# RN52_BO.net
KiCad netlist of a schematic drawn in EAGLE
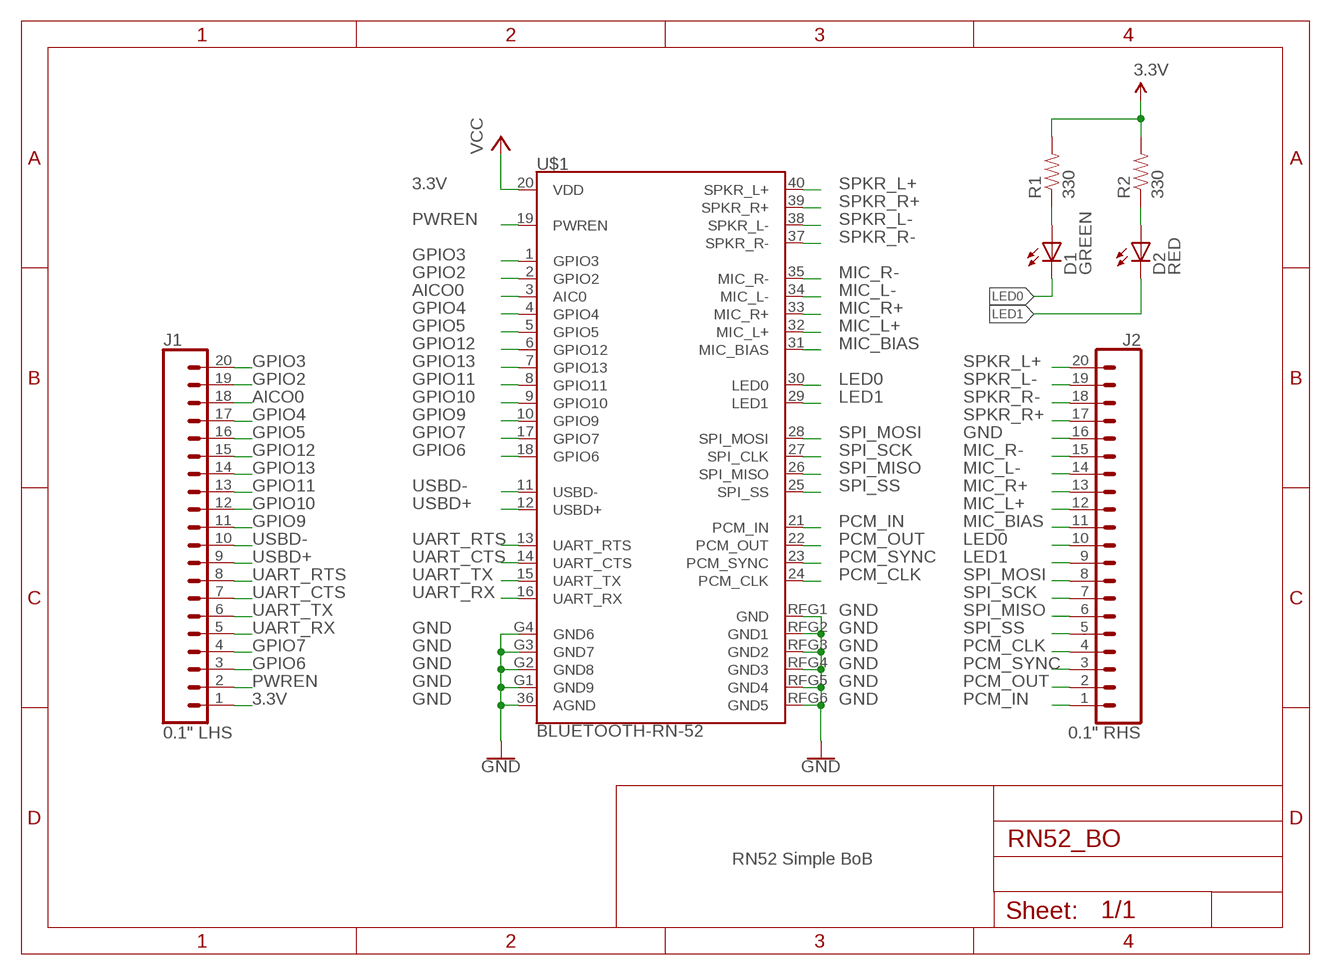
[diagram p0: schematic, sheet 1]

(export (version "E")
  (design (tool "Eeschema 10.0.6"))
  (components
    (comp (ref "D1")
      (value "GREEN")
      (footprint "eagle-import:LED-0603")
      (libsource (lib "eagle-import") (part "LED-GREEN0603"))
    )
    (comp (ref "D2")
      (value "RED")
      (footprint "eagle-import:LED-0603")
      (libsource (lib "eagle-import") (part "LED-RED0603"))
    )
    (comp (ref "J1")
      (value "0.1\" LHS")
      (footprint "eagle-import:1X20")
      (fields (field (name "TITLE") "0.1\" LHS"))
      (libsource (lib "eagle-import") (part "CONN_20"))
    )
    (comp (ref "J2")
      (value "0.1\" RHS")
      (footprint "eagle-import:1X20")
      (fields (field (name "TITLE") "0.1\" RHS"))
      (libsource (lib "eagle-import") (part "CONN_20"))
    )
    (comp (ref "R1")
      (value "330")
      (footprint "eagle-import:0603-RES")
      (libsource (lib "eagle-import") (part "RESISTOR0603-RES"))
    )
    (comp (ref "R2")
      (value "330")
      (footprint "eagle-import:0603-RES")
      (libsource (lib "eagle-import") (part "RESISTOR0603-RES"))
    )
    (comp (ref "U$1")
      (value "BLUETOOTH-RN-52")
      (footprint "eagle-import:RN-52")
      (libsource (lib "eagle-import") (part "BLUETOOTH-RN-52"))
    )
  )
  (nets
    (net (code "1") (name "/AICO0") (class "Default")
      (node (ref "J1") (pin "18") (pinfunction "18_18") (pintype "passive"))
      (node (ref "U$1") (pin "3") (pinfunction "AIC0_3") (pintype "bidirectional"))
    )
    (net (code "2") (name "/GPIO2") (class "Default")
      (node (ref "J1") (pin "19") (pinfunction "19_19") (pintype "passive"))
      (node (ref "U$1") (pin "2") (pinfunction "GPIO2_2") (pintype "bidirectional"))
    )
    (net (code "3") (name "/GPIO3") (class "Default")
      (node (ref "J1") (pin "20") (pinfunction "20_20") (pintype "passive"))
      (node (ref "U$1") (pin "1") (pinfunction "GPIO3_1") (pintype "bidirectional"))
    )
    (net (code "4") (name "/GPIO4") (class "Default")
      (node (ref "J1") (pin "17") (pinfunction "17_17") (pintype "passive"))
      (node (ref "U$1") (pin "4") (pinfunction "GPIO4_4") (pintype "bidirectional"))
    )
    (net (code "5") (name "/GPIO5") (class "Default")
      (node (ref "J1") (pin "16") (pinfunction "16_16") (pintype "passive"))
      (node (ref "U$1") (pin "5") (pinfunction "GPIO5_5") (pintype "bidirectional"))
    )
    (net (code "6") (name "/GPIO6") (class "Default")
      (node (ref "J1") (pin "3") (pinfunction "3_3") (pintype "passive"))
      (node (ref "U$1") (pin "18") (pinfunction "GPIO6_18") (pintype "bidirectional"))
    )
    (net (code "7") (name "/GPIO7") (class "Default")
      (node (ref "J1") (pin "4") (pinfunction "4_4") (pintype "passive"))
      (node (ref "U$1") (pin "17") (pinfunction "GPIO7_17") (pintype "bidirectional"))
    )
    (net (code "8") (name "/GPIO9") (class "Default")
      (node (ref "J1") (pin "11") (pinfunction "11_11") (pintype "passive"))
      (node (ref "U$1") (pin "10") (pinfunction "GPIO9_10") (pintype "bidirectional"))
    )
    (net (code "9") (name "/GPIO10") (class "Default")
      (node (ref "J1") (pin "12") (pinfunction "12_12") (pintype "passive"))
      (node (ref "U$1") (pin "9") (pinfunction "GPIO10_9") (pintype "bidirectional"))
    )
    (net (code "10") (name "/GPIO11") (class "Default")
      (node (ref "J1") (pin "13") (pinfunction "13_13") (pintype "passive"))
      (node (ref "U$1") (pin "8") (pinfunction "GPIO11_8") (pintype "bidirectional"))
    )
    (net (code "11") (name "/GPIO12") (class "Default")
      (node (ref "J1") (pin "15") (pinfunction "15_15") (pintype "passive"))
      (node (ref "U$1") (pin "6") (pinfunction "GPIO12_6") (pintype "bidirectional"))
    )
    (net (code "12") (name "/GPIO13") (class "Default")
      (node (ref "J1") (pin "14") (pinfunction "14_14") (pintype "passive"))
      (node (ref "U$1") (pin "7") (pinfunction "GPIO13_7") (pintype "bidirectional"))
    )
    (net (code "13") (name "/MIC_BIAS") (class "Default")
      (node (ref "J2") (pin "11") (pinfunction "11_11") (pintype "passive"))
      (node (ref "U$1") (pin "31") (pinfunction "MIC_BIAS_31") (pintype "bidirectional"))
    )
    (net (code "14") (name "/MIC_L+") (class "Default")
      (node (ref "J2") (pin "12") (pinfunction "12_12") (pintype "passive"))
      (node (ref "U$1") (pin "32") (pinfunction "MIC_L+_32") (pintype "bidirectional"))
    )
    (net (code "15") (name "/MIC_L-") (class "Default")
      (node (ref "J2") (pin "14") (pinfunction "14_14") (pintype "passive"))
      (node (ref "U$1") (pin "34") (pinfunction "MIC_L-_34") (pintype "bidirectional"))
    )
    (net (code "16") (name "/MIC_R+") (class "Default")
      (node (ref "J2") (pin "13") (pinfunction "13_13") (pintype "passive"))
      (node (ref "U$1") (pin "33") (pinfunction "MIC_R+_33") (pintype "bidirectional"))
    )
    (net (code "17") (name "/MIC_R-") (class "Default")
      (node (ref "J2") (pin "15") (pinfunction "15_15") (pintype "passive"))
      (node (ref "U$1") (pin "35") (pinfunction "MIC_R-_35") (pintype "bidirectional"))
    )
    (net (code "18") (name "/PCM_CLK") (class "Default")
      (node (ref "J2") (pin "4") (pinfunction "4_4") (pintype "passive"))
      (node (ref "U$1") (pin "24") (pinfunction "PCM_CLK_24") (pintype "bidirectional"))
    )
    (net (code "19") (name "/PCM_IN") (class "Default")
      (node (ref "J2") (pin "1") (pinfunction "1_1") (pintype "passive"))
      (node (ref "U$1") (pin "21") (pinfunction "PCM_IN_21") (pintype "bidirectional"))
    )
    (net (code "20") (name "/PCM_OUT") (class "Default")
      (node (ref "J2") (pin "2") (pinfunction "2_2") (pintype "passive"))
      (node (ref "U$1") (pin "22") (pinfunction "PCM_OUT_22") (pintype "bidirectional"))
    )
    (net (code "21") (name "/PCM_SYNC") (class "Default")
      (node (ref "J2") (pin "3") (pinfunction "3_3") (pintype "passive"))
      (node (ref "U$1") (pin "23") (pinfunction "PCM_SYNC_23") (pintype "bidirectional"))
    )
    (net (code "22") (name "/PWREN") (class "Default")
      (node (ref "J1") (pin "2") (pinfunction "2_2") (pintype "passive"))
      (node (ref "U$1") (pin "19") (pinfunction "PWREN_19") (pintype "bidirectional"))
    )
    (net (code "23") (name "/SPI_MISO") (class "Default")
      (node (ref "J2") (pin "6") (pinfunction "6_6") (pintype "passive"))
      (node (ref "U$1") (pin "26") (pinfunction "SPI_MISO_26") (pintype "bidirectional"))
    )
    (net (code "24") (name "/SPI_MOSI") (class "Default")
      (node (ref "J2") (pin "8") (pinfunction "8_8") (pintype "passive"))
      (node (ref "U$1") (pin "28") (pinfunction "SPI_MOSI_28") (pintype "bidirectional"))
    )
    (net (code "25") (name "/SPI_SCK") (class "Default")
      (node (ref "J2") (pin "7") (pinfunction "7_7") (pintype "passive"))
      (node (ref "U$1") (pin "27") (pinfunction "SPI_CLK_27") (pintype "bidirectional"))
    )
    (net (code "26") (name "/SPI_SS") (class "Default")
      (node (ref "J2") (pin "5") (pinfunction "5_5") (pintype "passive"))
      (node (ref "U$1") (pin "25") (pinfunction "SPI_SS_25") (pintype "bidirectional"))
    )
    (net (code "27") (name "/SPKR_L+") (class "Default")
      (node (ref "J2") (pin "20") (pinfunction "20_20") (pintype "passive"))
      (node (ref "U$1") (pin "40") (pinfunction "SPKR_L+_40") (pintype "bidirectional"))
    )
    (net (code "28") (name "/SPKR_L-") (class "Default")
      (node (ref "J2") (pin "19") (pinfunction "19_19") (pintype "passive"))
      (node (ref "U$1") (pin "38") (pinfunction "SPKR_L-_38") (pintype "bidirectional"))
    )
    (net (code "29") (name "/SPKR_R+") (class "Default")
      (node (ref "J2") (pin "17") (pinfunction "17_17") (pintype "passive"))
      (node (ref "U$1") (pin "39") (pinfunction "SPKR_R+_39") (pintype "bidirectional"))
    )
    (net (code "30") (name "/SPKR_R-") (class "Default")
      (node (ref "J2") (pin "18") (pinfunction "18_18") (pintype "passive"))
      (node (ref "U$1") (pin "37") (pinfunction "SPKR_R-_37") (pintype "bidirectional"))
    )
    (net (code "31") (name "/UART_CTS") (class "Default")
      (node (ref "J1") (pin "7") (pinfunction "7_7") (pintype "passive"))
      (node (ref "U$1") (pin "14") (pinfunction "UART_CTS_14") (pintype "bidirectional"))
    )
    (net (code "32") (name "/UART_RTS") (class "Default")
      (node (ref "J1") (pin "8") (pinfunction "8_8") (pintype "passive"))
      (node (ref "U$1") (pin "13") (pinfunction "UART_RTS_13") (pintype "bidirectional"))
    )
    (net (code "33") (name "/UART_RX") (class "Default")
      (node (ref "J1") (pin "5") (pinfunction "5_5") (pintype "passive"))
      (node (ref "U$1") (pin "16") (pinfunction "UART_RX_16") (pintype "bidirectional"))
    )
    (net (code "34") (name "/UART_TX") (class "Default")
      (node (ref "J1") (pin "6") (pinfunction "6_6") (pintype "passive"))
      (node (ref "U$1") (pin "15") (pinfunction "UART_TX_15") (pintype "bidirectional"))
    )
    (net (code "35") (name "/USBD+") (class "Default")
      (node (ref "J1") (pin "9") (pinfunction "9_9") (pintype "passive"))
      (node (ref "U$1") (pin "12") (pinfunction "USBD+_12") (pintype "bidirectional"))
    )
    (net (code "36") (name "/USBD-") (class "Default")
      (node (ref "J1") (pin "10") (pinfunction "10_10") (pintype "passive"))
      (node (ref "U$1") (pin "11") (pinfunction "USBD-_11") (pintype "bidirectional"))
    )
    (net (code "37") (name "3.3V") (class "Default")
      (node (ref "J1") (pin "1") (pinfunction "1_1") (pintype "passive"))
      (node (ref "R1") (pin "2") (pinfunction "2_2") (pintype "passive"))
      (node (ref "R2") (pin "2") (pinfunction "2_2") (pintype "passive"))
      (node (ref "U$1") (pin "20") (pinfunction "VDD_20") (pintype "bidirectional"))
    )
    (net (code "38") (name "GND") (class "Default")
      (node (ref "J2") (pin "16") (pinfunction "16_16") (pintype "passive"))
      (node (ref "U$1") (pin "36") (pinfunction "AGND_36") (pintype "bidirectional"))
      (node (ref "U$1") (pin "G1") (pinfunction "GND9_G1") (pintype "bidirectional"))
      (node (ref "U$1") (pin "G2") (pinfunction "GND8_G2") (pintype "bidirectional"))
      (node (ref "U$1") (pin "G3") (pinfunction "GND7_G3") (pintype "bidirectional"))
      (node (ref "U$1") (pin "G4") (pinfunction "GND6_G4") (pintype "bidirectional"))
      (node (ref "U$1") (pin "RFG1") (pinfunction "GND_RFG1") (pintype "bidirectional"))
      (node (ref "U$1") (pin "RFG2") (pinfunction "GND1_RFG2") (pintype "bidirectional"))
      (node (ref "U$1") (pin "RFG3") (pinfunction "GND2_RFG3") (pintype "bidirectional"))
      (node (ref "U$1") (pin "RFG4") (pinfunction "GND3_RFG4") (pintype "bidirectional"))
      (node (ref "U$1") (pin "RFG5") (pinfunction "GND4_RFG5") (pintype "bidirectional"))
      (node (ref "U$1") (pin "RFG6") (pinfunction "GND5_RFG6") (pintype "bidirectional"))
    )
    (net (code "39") (name "LED0") (class "Default")
      (node (ref "D1") (pin "C") (pinfunction "C_C") (pintype "passive"))
      (node (ref "J2") (pin "10") (pinfunction "10_10") (pintype "passive"))
      (node (ref "U$1") (pin "30") (pinfunction "LED0_30") (pintype "bidirectional"))
    )
    (net (code "40") (name "LED1") (class "Default")
      (node (ref "D2") (pin "C") (pinfunction "C_C") (pintype "passive"))
      (node (ref "J2") (pin "9") (pinfunction "9_9") (pintype "passive"))
      (node (ref "U$1") (pin "29") (pinfunction "LED1_29") (pintype "bidirectional"))
    )
    (net (code "41") (name "Net-(D1-PadA)") (class "Default")
      (node (ref "D1") (pin "A") (pinfunction "A_A") (pintype "passive"))
      (node (ref "R1") (pin "1") (pinfunction "1_1") (pintype "passive"))
    )
    (net (code "42") (name "Net-(D2-PadA)") (class "Default")
      (node (ref "D2") (pin "A") (pinfunction "A_A") (pintype "passive"))
      (node (ref "R2") (pin "1") (pinfunction "1_1") (pintype "passive"))
    )
  )
)
